# AVRI2CIO_V0_2_LEVEL1.net
KiCad netlist of a schematic drawn in EAGLE
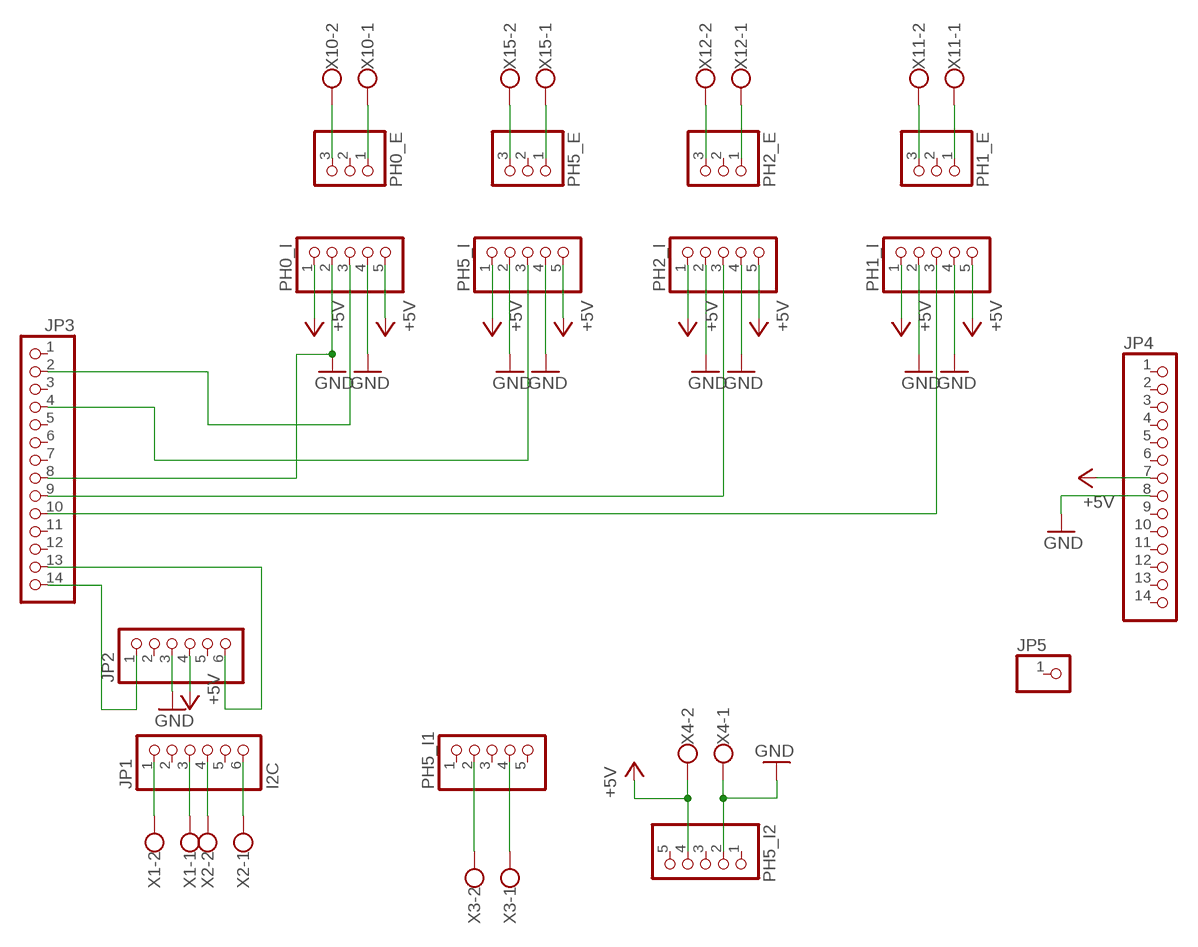
[diagram p0: schematic, sheet 1]

(export (version "E")
  (design (tool "Eeschema 10.0.6"))
  (components
    (comp (ref "JP1")
      (value "I2C")
      (footprint "eagle-import:1X06")
      (libsource (lib "eagle-import") (part "PINHD-1X6"))
    )
    (comp (ref "JP2")
      (value "PINHD-1X6")
      (footprint "eagle-import:1X06")
      (libsource (lib "eagle-import") (part "PINHD-1X6"))
    )
    (comp (ref "JP3")
      (value "PINHD-1X14")
      (footprint "eagle-import:1X14")
      (libsource (lib "eagle-import") (part "PINHD-1X14"))
    )
    (comp (ref "JP4")
      (value "PINHD-1X14")
      (footprint "eagle-import:1X14")
      (libsource (lib "eagle-import") (part "PINHD-1X14"))
    )
    (comp (ref "JP5")
      (value "PINHD-1X1")
      (footprint "eagle-import:1X01")
      (libsource (lib "eagle-import") (part "PINHD-1X1"))
    )
    (comp (ref "PH0_E")
      (value "PINHD-1X3")
      (footprint "eagle-import:1X03")
      (libsource (lib "eagle-import") (part "PINHD-1X3"))
    )
    (comp (ref "PH0_I")
      (value "PINHD-1X5")
      (footprint "eagle-import:1X05")
      (libsource (lib "eagle-import") (part "PINHD-1X5"))
    )
    (comp (ref "PH1_E")
      (value "PINHD-1X3")
      (footprint "eagle-import:1X03")
      (libsource (lib "eagle-import") (part "PINHD-1X3"))
    )
    (comp (ref "PH1_I")
      (value "PINHD-1X5")
      (footprint "eagle-import:1X05")
      (libsource (lib "eagle-import") (part "PINHD-1X5"))
    )
    (comp (ref "PH2_E")
      (value "PINHD-1X3")
      (footprint "eagle-import:1X03")
      (libsource (lib "eagle-import") (part "PINHD-1X3"))
    )
    (comp (ref "PH2_I")
      (value "PINHD-1X5")
      (footprint "eagle-import:1X05")
      (libsource (lib "eagle-import") (part "PINHD-1X5"))
    )
    (comp (ref "PH5_E")
      (value "PINHD-1X3")
      (footprint "eagle-import:1X03")
      (libsource (lib "eagle-import") (part "PINHD-1X3"))
    )
    (comp (ref "PH5_I")
      (value "PINHD-1X5")
      (footprint "eagle-import:1X05")
      (libsource (lib "eagle-import") (part "PINHD-1X5"))
    )
    (comp (ref "PH5_I1")
      (value "PINHD-1X5")
      (footprint "eagle-import:1X05")
      (libsource (lib "eagle-import") (part "PINHD-1X5"))
    )
    (comp (ref "PH5_I2")
      (value "PINHD-1X5")
      (footprint "eagle-import:1X05")
      (libsource (lib "eagle-import") (part "PINHD-1X5"))
    )
    (comp (ref "X1")
      (value "W237-102")
      (footprint "eagle-import:W237-102")
      (fields (field (name "MPN") "237-102"))
      (libsource (lib "eagle-import") (part "W237-102"))
    )
    (comp (ref "X2")
      (value "W237-102")
      (footprint "eagle-import:W237-102")
      (fields (field (name "MPN") "237-102"))
      (libsource (lib "eagle-import") (part "W237-102"))
    )
    (comp (ref "X3")
      (value "W237-102")
      (footprint "eagle-import:W237-102")
      (fields (field (name "MPN") "237-102"))
      (libsource (lib "eagle-import") (part "W237-102"))
    )
    (comp (ref "X4")
      (value "W237-102")
      (footprint "eagle-import:W237-102")
      (fields (field (name "MPN") "237-102"))
      (libsource (lib "eagle-import") (part "W237-102"))
    )
    (comp (ref "X10")
      (value "W237-102")
      (footprint "eagle-import:W237-102")
      (fields
        (field (name "MPN") "237-102")
        (field (name "MPN_1") "237-102")
        (field (name "OC_FARNELL") "unknown")
        (field (name "OC_NEWARK") "70K9898")
      )
      (libsource (lib "eagle-import") (part "W237-102"))
    )
    (comp (ref "X11")
      (value "W237-102")
      (footprint "eagle-import:W237-102")
      (fields (field (name "MPN") "237-102"))
      (libsource (lib "eagle-import") (part "W237-102"))
    )
    (comp (ref "X12")
      (value "W237-102")
      (footprint "eagle-import:W237-102")
      (fields (field (name "MPN") "237-102"))
      (libsource (lib "eagle-import") (part "W237-102"))
    )
    (comp (ref "X15")
      (value "W237-102")
      (footprint "eagle-import:W237-102")
      (fields (field (name "MPN") "237-102"))
      (libsource (lib "eagle-import") (part "W237-102"))
    )
  )
  (nets
    (net (code "1") (name "+5V") (class "Default")
      (node (ref "JP2") (pin "4") (pinfunction "4_4") (pintype "passive"))
      (node (ref "JP4") (pin "7") (pinfunction "7_7") (pintype "passive"))
      (node (ref "PH0_I") (pin "1") (pinfunction "1_1") (pintype "passive"))
      (node (ref "PH0_I") (pin "5") (pinfunction "5_5") (pintype "passive"))
      (node (ref "PH1_I") (pin "1") (pinfunction "1_1") (pintype "passive"))
      (node (ref "PH1_I") (pin "5") (pinfunction "5_5") (pintype "passive"))
      (node (ref "PH2_I") (pin "1") (pinfunction "1_1") (pintype "passive"))
      (node (ref "PH2_I") (pin "5") (pinfunction "5_5") (pintype "passive"))
      (node (ref "PH5_I") (pin "1") (pinfunction "1_1") (pintype "passive"))
      (node (ref "PH5_I") (pin "5") (pinfunction "5_5") (pintype "passive"))
      (node (ref "PH5_I2") (pin "4") (pinfunction "4_4") (pintype "passive"))
      (node (ref "X4") (pin "2") (pinfunction "KL_2") (pintype "passive"))
    )
    (net (code "2") (name "GND") (class "Default")
      (node (ref "JP2") (pin "3") (pinfunction "3_3") (pintype "passive"))
      (node (ref "JP3") (pin "8") (pinfunction "8_8") (pintype "passive"))
      (node (ref "JP4") (pin "8") (pinfunction "8_8") (pintype "passive"))
      (node (ref "PH0_I") (pin "2") (pinfunction "2_2") (pintype "passive"))
      (node (ref "PH0_I") (pin "4") (pinfunction "4_4") (pintype "passive"))
      (node (ref "PH1_I") (pin "2") (pinfunction "2_2") (pintype "passive"))
      (node (ref "PH1_I") (pin "4") (pinfunction "4_4") (pintype "passive"))
      (node (ref "PH2_I") (pin "2") (pinfunction "2_2") (pintype "passive"))
      (node (ref "PH2_I") (pin "4") (pinfunction "4_4") (pintype "passive"))
      (node (ref "PH5_I") (pin "2") (pinfunction "2_2") (pintype "passive"))
      (node (ref "PH5_I") (pin "4") (pinfunction "4_4") (pintype "passive"))
      (node (ref "PH5_I2") (pin "2") (pinfunction "2_2") (pintype "passive"))
      (node (ref "X4") (pin "1") (pinfunction "KL_1") (pintype "passive"))
    )
    (net (code "3") (name "Net-(JP2-Pad1)") (class "Default")
      (node (ref "JP2") (pin "1") (pinfunction "1_1") (pintype "passive"))
      (node (ref "JP3") (pin "14") (pinfunction "14_14") (pintype "passive"))
    )
    (net (code "4") (name "Net-(JP2-Pad6)") (class "Default")
      (node (ref "JP2") (pin "6") (pinfunction "6_6") (pintype "passive"))
      (node (ref "JP3") (pin "13") (pinfunction "13_13") (pintype "passive"))
    )
    (net (code "5") (name "Net-(JP3-Pad2)") (class "Default")
      (node (ref "JP3") (pin "2") (pinfunction "2_2") (pintype "passive"))
      (node (ref "PH0_I") (pin "3") (pinfunction "3_3") (pintype "passive"))
    )
    (net (code "6") (name "Net-(JP3-Pad4)") (class "Default")
      (node (ref "JP3") (pin "4") (pinfunction "4_4") (pintype "passive"))
      (node (ref "PH5_I") (pin "3") (pinfunction "3_3") (pintype "passive"))
    )
    (net (code "7") (name "Net-(JP3-Pad9)") (class "Default")
      (node (ref "JP3") (pin "9") (pinfunction "9_9") (pintype "passive"))
      (node (ref "PH2_I") (pin "3") (pinfunction "3_3") (pintype "passive"))
    )
    (net (code "8") (name "Net-(JP3-Pad10)") (class "Default")
      (node (ref "JP3") (pin "10") (pinfunction "10_10") (pintype "passive"))
      (node (ref "PH1_I") (pin "3") (pinfunction "3_3") (pintype "passive"))
    )
    (net (code "9") (name "Net-(X1A-KL)") (class "Default")
      (node (ref "JP1") (pin "3") (pinfunction "3_3") (pintype "passive"))
      (node (ref "X1") (pin "1") (pinfunction "KL_1") (pintype "passive"))
    )
    (net (code "10") (name "Net-(X1B-KL)") (class "Default")
      (node (ref "JP1") (pin "1") (pinfunction "1_1") (pintype "passive"))
      (node (ref "X1") (pin "2") (pinfunction "KL_2") (pintype "passive"))
    )
    (net (code "11") (name "Net-(X2A-KL)") (class "Default")
      (node (ref "JP1") (pin "6") (pinfunction "6_6") (pintype "passive"))
      (node (ref "X2") (pin "1") (pinfunction "KL_1") (pintype "passive"))
    )
    (net (code "12") (name "Net-(X2B-KL)") (class "Default")
      (node (ref "JP1") (pin "4") (pinfunction "4_4") (pintype "passive"))
      (node (ref "X2") (pin "2") (pinfunction "KL_2") (pintype "passive"))
    )
    (net (code "13") (name "Net-(X3A-KL)") (class "Default")
      (node (ref "PH5_I1") (pin "4") (pinfunction "4_4") (pintype "passive"))
      (node (ref "X3") (pin "1") (pinfunction "KL_1") (pintype "passive"))
    )
    (net (code "14") (name "Net-(X3B-KL)") (class "Default")
      (node (ref "PH5_I1") (pin "2") (pinfunction "2_2") (pintype "passive"))
      (node (ref "X3") (pin "2") (pinfunction "KL_2") (pintype "passive"))
    )
    (net (code "15") (name "Net-(X10A-KL)") (class "Default")
      (node (ref "PH0_E") (pin "1") (pinfunction "1_1") (pintype "passive"))
      (node (ref "X10") (pin "1") (pinfunction "KL_1") (pintype "passive"))
    )
    (net (code "16") (name "Net-(X10B-KL)") (class "Default")
      (node (ref "PH0_E") (pin "3") (pinfunction "3_3") (pintype "passive"))
      (node (ref "X10") (pin "2") (pinfunction "KL_2") (pintype "passive"))
    )
    (net (code "17") (name "Net-(X11A-KL)") (class "Default")
      (node (ref "PH1_E") (pin "1") (pinfunction "1_1") (pintype "passive"))
      (node (ref "X11") (pin "1") (pinfunction "KL_1") (pintype "passive"))
    )
    (net (code "18") (name "Net-(X11B-KL)") (class "Default")
      (node (ref "PH1_E") (pin "3") (pinfunction "3_3") (pintype "passive"))
      (node (ref "X11") (pin "2") (pinfunction "KL_2") (pintype "passive"))
    )
    (net (code "19") (name "Net-(X12A-KL)") (class "Default")
      (node (ref "PH2_E") (pin "1") (pinfunction "1_1") (pintype "passive"))
      (node (ref "X12") (pin "1") (pinfunction "KL_1") (pintype "passive"))
    )
    (net (code "20") (name "Net-(X12B-KL)") (class "Default")
      (node (ref "PH2_E") (pin "3") (pinfunction "3_3") (pintype "passive"))
      (node (ref "X12") (pin "2") (pinfunction "KL_2") (pintype "passive"))
    )
    (net (code "21") (name "Net-(X15A-KL)") (class "Default")
      (node (ref "PH5_E") (pin "1") (pinfunction "1_1") (pintype "passive"))
      (node (ref "X15") (pin "1") (pinfunction "KL_1") (pintype "passive"))
    )
    (net (code "22") (name "Net-(X15B-KL)") (class "Default")
      (node (ref "PH5_E") (pin "3") (pinfunction "3_3") (pintype "passive"))
      (node (ref "X15") (pin "2") (pinfunction "KL_2") (pintype "passive"))
    )
    (net (code "23") (name "unconnected-(JP1-Pad2)") (class "Default")
      (node (ref "JP1") (pin "2") (pinfunction "2_2") (pintype "passive"))
    )
    (net (code "24") (name "unconnected-(JP1-Pad5)") (class "Default")
      (node (ref "JP1") (pin "5") (pinfunction "5_5") (pintype "passive"))
    )
    (net (code "25") (name "unconnected-(JP2-Pad2)") (class "Default")
      (node (ref "JP2") (pin "2") (pinfunction "2_2") (pintype "passive"))
    )
    (net (code "26") (name "unconnected-(JP2-Pad5)") (class "Default")
      (node (ref "JP2") (pin "5") (pinfunction "5_5") (pintype "passive"))
    )
    (net (code "27") (name "unconnected-(JP3-Pad1)") (class "Default")
      (node (ref "JP3") (pin "1") (pinfunction "1_1") (pintype "passive"))
    )
    (net (code "28") (name "unconnected-(JP3-Pad3)") (class "Default")
      (node (ref "JP3") (pin "3") (pinfunction "3_3") (pintype "passive"))
    )
    (net (code "29") (name "unconnected-(JP3-Pad5)") (class "Default")
      (node (ref "JP3") (pin "5") (pinfunction "5_5") (pintype "passive"))
    )
    (net (code "30") (name "unconnected-(JP3-Pad6)") (class "Default")
      (node (ref "JP3") (pin "6") (pinfunction "6_6") (pintype "passive"))
    )
    (net (code "31") (name "unconnected-(JP3-Pad7)") (class "Default")
      (node (ref "JP3") (pin "7") (pinfunction "7_7") (pintype "passive"))
    )
    (net (code "32") (name "unconnected-(JP3-Pad11)") (class "Default")
      (node (ref "JP3") (pin "11") (pinfunction "11_11") (pintype "passive"))
    )
    (net (code "33") (name "unconnected-(JP3-Pad12)") (class "Default")
      (node (ref "JP3") (pin "12") (pinfunction "12_12") (pintype "passive"))
    )
    (net (code "34") (name "unconnected-(JP4-Pad1)") (class "Default")
      (node (ref "JP4") (pin "1") (pinfunction "1_1") (pintype "passive"))
    )
    (net (code "35") (name "unconnected-(JP4-Pad2)") (class "Default")
      (node (ref "JP4") (pin "2") (pinfunction "2_2") (pintype "passive"))
    )
    (net (code "36") (name "unconnected-(JP4-Pad3)") (class "Default")
      (node (ref "JP4") (pin "3") (pinfunction "3_3") (pintype "passive"))
    )
    (net (code "37") (name "unconnected-(JP4-Pad4)") (class "Default")
      (node (ref "JP4") (pin "4") (pinfunction "4_4") (pintype "passive"))
    )
    (net (code "38") (name "unconnected-(JP4-Pad5)") (class "Default")
      (node (ref "JP4") (pin "5") (pinfunction "5_5") (pintype "passive"))
    )
    (net (code "39") (name "unconnected-(JP4-Pad6)") (class "Default")
      (node (ref "JP4") (pin "6") (pinfunction "6_6") (pintype "passive"))
    )
    (net (code "40") (name "unconnected-(JP4-Pad9)") (class "Default")
      (node (ref "JP4") (pin "9") (pinfunction "9_9") (pintype "passive"))
    )
    (net (code "41") (name "unconnected-(JP4-Pad10)") (class "Default")
      (node (ref "JP4") (pin "10") (pinfunction "10_10") (pintype "passive"))
    )
    (net (code "42") (name "unconnected-(JP4-Pad11)") (class "Default")
      (node (ref "JP4") (pin "11") (pinfunction "11_11") (pintype "passive"))
    )
    (net (code "43") (name "unconnected-(JP4-Pad12)") (class "Default")
      (node (ref "JP4") (pin "12") (pinfunction "12_12") (pintype "passive"))
    )
    (net (code "44") (name "unconnected-(JP4-Pad13)") (class "Default")
      (node (ref "JP4") (pin "13") (pinfunction "13_13") (pintype "passive"))
    )
    (net (code "45") (name "unconnected-(JP4-Pad14)") (class "Default")
      (node (ref "JP4") (pin "14") (pinfunction "14_14") (pintype "passive"))
    )
    (net (code "46") (name "unconnected-(JP5-Pad1)") (class "Default")
      (node (ref "JP5") (pin "1") (pinfunction "1_1") (pintype "passive"))
    )
    (net (code "47") (name "unconnected-(PH0_E-Pad2)") (class "Default")
      (node (ref "PH0_E") (pin "2") (pinfunction "2_2") (pintype "passive"))
    )
    (net (code "48") (name "unconnected-(PH1_E-Pad2)") (class "Default")
      (node (ref "PH1_E") (pin "2") (pinfunction "2_2") (pintype "passive"))
    )
    (net (code "49") (name "unconnected-(PH2_E-Pad2)") (class "Default")
      (node (ref "PH2_E") (pin "2") (pinfunction "2_2") (pintype "passive"))
    )
    (net (code "50") (name "unconnected-(PH5_E-Pad2)") (class "Default")
      (node (ref "PH5_E") (pin "2") (pinfunction "2_2") (pintype "passive"))
    )
    (net (code "51") (name "unconnected-(PH5_I1-Pad1)") (class "Default")
      (node (ref "PH5_I1") (pin "1") (pinfunction "1_1") (pintype "passive"))
    )
    (net (code "52") (name "unconnected-(PH5_I1-Pad3)") (class "Default")
      (node (ref "PH5_I1") (pin "3") (pinfunction "3_3") (pintype "passive"))
    )
    (net (code "53") (name "unconnected-(PH5_I1-Pad5)") (class "Default")
      (node (ref "PH5_I1") (pin "5") (pinfunction "5_5") (pintype "passive"))
    )
    (net (code "54") (name "unconnected-(PH5_I2-Pad1)") (class "Default")
      (node (ref "PH5_I2") (pin "1") (pinfunction "1_1") (pintype "passive"))
    )
    (net (code "55") (name "unconnected-(PH5_I2-Pad3)") (class "Default")
      (node (ref "PH5_I2") (pin "3") (pinfunction "3_3") (pintype "passive"))
    )
    (net (code "56") (name "unconnected-(PH5_I2-Pad5)") (class "Default")
      (node (ref "PH5_I2") (pin "5") (pinfunction "5_5") (pintype "passive"))
    )
  )
)
